# 1_1_1_Interface_board_MCU.net
KiCad netlist of a schematic drawn in Altium Designer
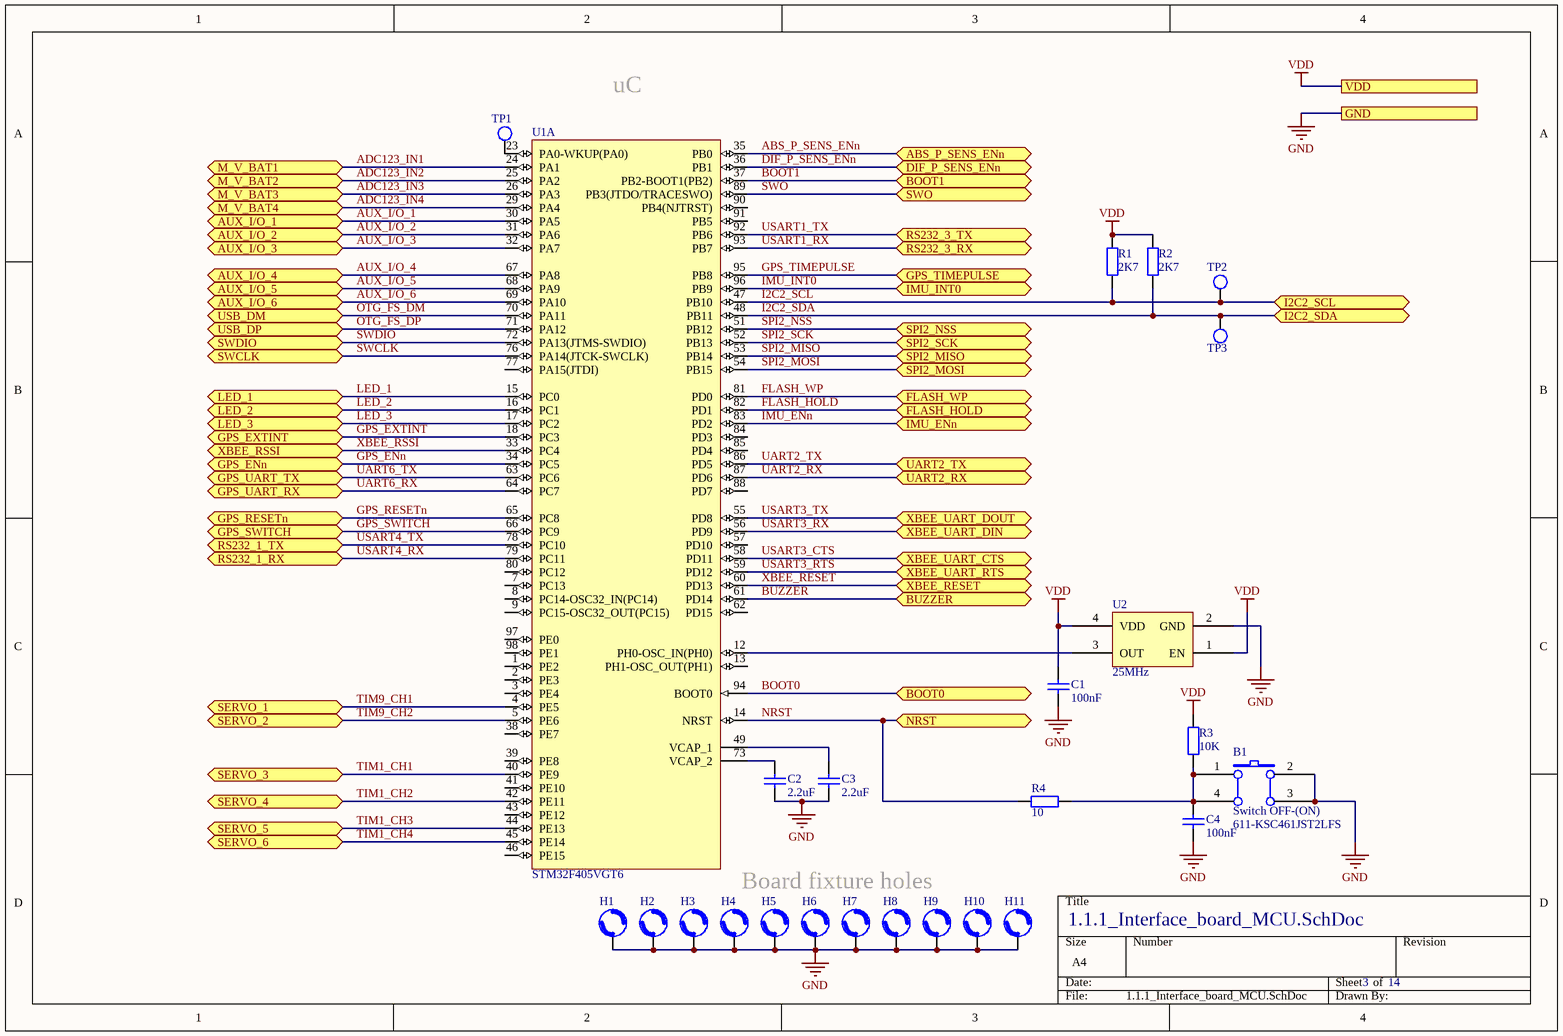
[diagram p0: 1.1.1_Interface_board_MCU.SchDoc]

(export (version "E")
  (design (tool "Eeschema 10.0.6"))
  (components
    (comp (ref "B1")
      (value "Switch OFF-(ON)")
      (footprint "Switch CK")
      (description "OFF-(ON)")
      (fields (field (name "SUPPLIER PART NUMBER 1") "611-KSC461JST2LFS"))
      (libsource (lib "Rocket_library") (part "Switch OFF-(ON)"))
    )
    (comp (ref "C1")
      (value "100nF")
      (footprint "CAP0603R")
      (description "Capacitor")
      (libsource (lib "Rocket_library") (part "C_100nF"))
    )
    (comp (ref "C2")
      (value "2.2uF")
      (footprint "CAP1206W")
      (description "Capacitor")
      (libsource (lib "Rocket_library") (part "C_2.2uF_1206"))
    )
    (comp (ref "C3")
      (value "2.2uF")
      (footprint "CAP1206W")
      (description "Capacitor")
      (libsource (lib "Rocket_library") (part "C_2.2uF_1206"))
    )
    (comp (ref "C4")
      (value "100nF")
      (footprint "CAP0603R")
      (description "Capacitor")
      (libsource (lib "Rocket_library") (part "C_100nF"))
    )
    (comp (ref "H1")
      (value "Hole_3.2mm")
      (footprint "HOLE_3.2mm")
      (libsource (lib "Rocket_library") (part "Hole_3.2mm"))
    )
    (comp (ref "H2")
      (value "Hole_3.2mm")
      (footprint "HOLE_3.2mm")
      (libsource (lib "Rocket_library") (part "Hole_3.2mm"))
    )
    (comp (ref "H3")
      (value "Hole_3.2mm")
      (footprint "HOLE_3.2mm")
      (libsource (lib "Rocket_library") (part "Hole_3.2mm"))
    )
    (comp (ref "H4")
      (value "Hole_3.2mm")
      (footprint "HOLE_3.2mm")
      (libsource (lib "Rocket_library") (part "Hole_3.2mm"))
    )
    (comp (ref "H5")
      (value "Hole_3.2mm")
      (footprint "HOLE_3.2mm")
      (libsource (lib "Rocket_library") (part "Hole_3.2mm"))
    )
    (comp (ref "H6")
      (value "Hole_3.2mm")
      (footprint "HOLE_3.2mm")
      (libsource (lib "Rocket_library") (part "Hole_3.2mm"))
    )
    (comp (ref "H7")
      (value "Hole_3.2mm")
      (footprint "HOLE_3.2mm")
      (libsource (lib "Rocket_library") (part "Hole_3.2mm"))
    )
    (comp (ref "H8")
      (value "Hole_3.2mm")
      (footprint "HOLE_3.2mm")
      (libsource (lib "Rocket_library") (part "Hole_3.2mm"))
    )
    (comp (ref "H9")
      (value "Hole_3.2mm")
      (footprint "HOLE_3.2mm")
      (libsource (lib "Rocket_library") (part "Hole_3.2mm"))
    )
    (comp (ref "H10")
      (value "Hole_3.2mm")
      (footprint "HOLE_3.2mm")
      (libsource (lib "Rocket_library") (part "Hole_3.2mm"))
    )
    (comp (ref "H11")
      (value "Hole_3.2mm")
      (footprint "HOLE_3.2mm")
      (libsource (lib "Rocket_library") (part "Hole_3.2mm"))
    )
    (comp (ref "R1")
      (value "2K7")
      (footprint "0603")
      (description "0.1W 2K7")
      (libsource (lib "Rocket_library") (part "R_0603_01W_2K7"))
    )
    (comp (ref "R2")
      (value "2K7")
      (footprint "0603")
      (description "0.1W 2K7")
      (libsource (lib "Rocket_library") (part "R_0603_01W_2K7"))
    )
    (comp (ref "R3")
      (value "10K")
      (footprint "0603")
      (description "0.1W 10K")
      (libsource (lib "Rocket_library") (part "R_0603_01W_10K"))
    )
    (comp (ref "R4")
      (value "10")
      (footprint "0603")
      (description "0.25W 10Ohm")
      (libsource (lib "Rocket_library") (part "R_0603_025W_10Ohm"))
    )
    (comp (ref "TP1")
      (value "Test point")
      (footprint "TP")
      (libsource (lib "Rocket_library") (part "Test point"))
    )
    (comp (ref "TP2")
      (value "Test point")
      (footprint "TP")
      (libsource (lib "Rocket_library") (part "Test point"))
    )
    (comp (ref "TP3")
      (value "Test point")
      (footprint "TP")
      (libsource (lib "Rocket_library") (part "Test point"))
    )
    (comp (ref "U1")
      (value "STM32F405VGT6")
      (footprint "STM-LQFP100_N")
      (fields (field (name "MANUFACTURER") "STMicroelectronics"))
      (libsource (lib "STMicroelectronics STM32 F4") (part "STM32F405VGT6"))
    )
    (comp (ref "U2")
      (value "25MHz")
      (footprint "SMD_3.2X2.5MM_4P")
      (description "Osc")
      (libsource (lib "Rocket_library") (part "DSC1001CI2-025.0000"))
    )
  )
  (nets
    (net (code "1") (name "/ABS_P_SENS_ENn") (class "Default")
      (node (ref "U1") (pin "35") (pinfunction "PB0_35") (pintype "bidirectional"))
    )
    (net (code "2") (name "/ADC123_IN1") (class "Default")
      (node (ref "U1") (pin "24") (pinfunction "PA1_24") (pintype "bidirectional"))
    )
    (net (code "3") (name "/ADC123_IN2") (class "Default")
      (node (ref "U1") (pin "25") (pinfunction "PA2_25") (pintype "bidirectional"))
    )
    (net (code "4") (name "/ADC123_IN3") (class "Default")
      (node (ref "U1") (pin "26") (pinfunction "PA3_26") (pintype "bidirectional"))
    )
    (net (code "5") (name "/ADC123_IN4") (class "Default")
      (node (ref "U1") (pin "29") (pinfunction "PA4_29") (pintype "bidirectional"))
    )
    (net (code "6") (name "/AUX_I{slash}O_1") (class "Default")
      (node (ref "U1") (pin "30") (pinfunction "PA5_30") (pintype "bidirectional"))
    )
    (net (code "7") (name "/AUX_I{slash}O_2") (class "Default")
      (node (ref "U1") (pin "31") (pinfunction "PA6_31") (pintype "bidirectional"))
    )
    (net (code "8") (name "/AUX_I{slash}O_3") (class "Default")
      (node (ref "U1") (pin "32") (pinfunction "PA7_32") (pintype "bidirectional"))
    )
    (net (code "9") (name "/AUX_I{slash}O_4") (class "Default")
      (node (ref "U1") (pin "67") (pinfunction "PA8_67") (pintype "bidirectional"))
    )
    (net (code "10") (name "/AUX_I{slash}O_5") (class "Default")
      (node (ref "U1") (pin "68") (pinfunction "PA9_68") (pintype "bidirectional"))
    )
    (net (code "11") (name "/AUX_I{slash}O_6") (class "Default")
      (node (ref "U1") (pin "69") (pinfunction "PA10_69") (pintype "bidirectional"))
    )
    (net (code "12") (name "/BOOT0") (class "Default")
      (node (ref "U1") (pin "94") (pinfunction "BOOT0_94") (pintype "input"))
    )
    (net (code "13") (name "/BOOT1") (class "Default")
      (node (ref "U1") (pin "37") (pinfunction "PB2-BOOT1(PB2)_37") (pintype "bidirectional"))
    )
    (net (code "14") (name "/BUZZER") (class "Default")
      (node (ref "U1") (pin "61") (pinfunction "PD14_61") (pintype "bidirectional"))
    )
    (net (code "15") (name "/DIF_P_SENS_ENn") (class "Default")
      (node (ref "U1") (pin "36") (pinfunction "PB1_36") (pintype "bidirectional"))
    )
    (net (code "16") (name "/FLASH_HOLD") (class "Default")
      (node (ref "U1") (pin "82") (pinfunction "PD1_82") (pintype "bidirectional"))
    )
    (net (code "17") (name "/FLASH_WP") (class "Default")
      (node (ref "U1") (pin "81") (pinfunction "PD0_81") (pintype "bidirectional"))
    )
    (net (code "18") (name "/GPS_ENn") (class "Default")
      (node (ref "U1") (pin "34") (pinfunction "PC5_34") (pintype "bidirectional"))
    )
    (net (code "19") (name "/GPS_EXTINT") (class "Default")
      (node (ref "U1") (pin "18") (pinfunction "PC3_18") (pintype "bidirectional"))
    )
    (net (code "20") (name "/GPS_RESETn") (class "Default")
      (node (ref "U1") (pin "65") (pinfunction "PC8_65") (pintype "bidirectional"))
    )
    (net (code "21") (name "/GPS_SWITCH") (class "Default")
      (node (ref "U1") (pin "66") (pinfunction "PC9_66") (pintype "bidirectional"))
    )
    (net (code "22") (name "/GPS_TIMEPULSE") (class "Default")
      (node (ref "U1") (pin "95") (pinfunction "PB8_95") (pintype "bidirectional"))
    )
    (net (code "23") (name "/I2C2_SCL") (class "Default")
      (node (ref "R1") (pin "1") (pinfunction "1_1") (pintype "passive"))
      (node (ref "TP2") (pin "1") (pinfunction "1_1") (pintype "passive"))
      (node (ref "U1") (pin "47") (pinfunction "PB10_47") (pintype "bidirectional"))
    )
    (net (code "24") (name "/I2C2_SDA") (class "Default")
      (node (ref "R2") (pin "1") (pinfunction "1_1") (pintype "passive"))
      (node (ref "TP3") (pin "1") (pinfunction "1_1") (pintype "passive"))
      (node (ref "U1") (pin "48") (pinfunction "PB11_48") (pintype "bidirectional"))
    )
    (net (code "25") (name "/IMU_ENn") (class "Default")
      (node (ref "U1") (pin "83") (pinfunction "PD2_83") (pintype "bidirectional"))
    )
    (net (code "26") (name "/IMU_INT0") (class "Default")
      (node (ref "U1") (pin "96") (pinfunction "PB9_96") (pintype "bidirectional"))
    )
    (net (code "27") (name "/LED_1") (class "Default")
      (node (ref "U1") (pin "15") (pinfunction "PC0_15") (pintype "bidirectional"))
    )
    (net (code "28") (name "/LED_2") (class "Default")
      (node (ref "U1") (pin "16") (pinfunction "PC1_16") (pintype "bidirectional"))
    )
    (net (code "29") (name "/LED_3") (class "Default")
      (node (ref "U1") (pin "17") (pinfunction "PC2_17") (pintype "bidirectional"))
    )
    (net (code "30") (name "/NRST") (class "Default")
      (node (ref "R4") (pin "1") (pinfunction "1_1") (pintype "passive"))
      (node (ref "U1") (pin "14") (pinfunction "NRST_14") (pintype "bidirectional"))
    )
    (net (code "31") (name "/OTG_FS_DM") (class "Default")
      (node (ref "U1") (pin "70") (pinfunction "PA11_70") (pintype "bidirectional"))
    )
    (net (code "32") (name "/OTG_FS_DP") (class "Default")
      (node (ref "U1") (pin "71") (pinfunction "PA12_71") (pintype "bidirectional"))
    )
    (net (code "33") (name "/SPI2_MISO") (class "Default")
      (node (ref "U1") (pin "53") (pinfunction "PB14_53") (pintype "bidirectional"))
    )
    (net (code "34") (name "/SPI2_MOSI") (class "Default")
      (node (ref "U1") (pin "54") (pinfunction "PB15_54") (pintype "bidirectional"))
    )
    (net (code "35") (name "/SPI2_NSS") (class "Default")
      (node (ref "U1") (pin "51") (pinfunction "PB12_51") (pintype "bidirectional"))
    )
    (net (code "36") (name "/SPI2_SCK") (class "Default")
      (node (ref "U1") (pin "52") (pinfunction "PB13_52") (pintype "bidirectional"))
    )
    (net (code "37") (name "/SWCLK") (class "Default")
      (node (ref "U1") (pin "76") (pinfunction "PA14(JTCK-SWCLK)_76") (pintype "bidirectional"))
    )
    (net (code "38") (name "/SWDIO") (class "Default")
      (node (ref "U1") (pin "72") (pinfunction "PA13(JTMS-SWDIO)_72") (pintype "bidirectional"))
    )
    (net (code "39") (name "/SWO") (class "Default")
      (node (ref "U1") (pin "89") (pinfunction "PB3(JTDO/TRACESWO)_89") (pintype "bidirectional"))
    )
    (net (code "40") (name "/TIM1_CH1") (class "Default")
      (node (ref "U1") (pin "40") (pinfunction "PE9_40") (pintype "bidirectional"))
    )
    (net (code "41") (name "/TIM1_CH2") (class "Default")
      (node (ref "U1") (pin "42") (pinfunction "PE11_42") (pintype "bidirectional"))
    )
    (net (code "42") (name "/TIM1_CH3") (class "Default")
      (node (ref "U1") (pin "44") (pinfunction "PE13_44") (pintype "bidirectional"))
    )
    (net (code "43") (name "/TIM1_CH4") (class "Default")
      (node (ref "U1") (pin "45") (pinfunction "PE14_45") (pintype "bidirectional"))
    )
    (net (code "44") (name "/TIM9_CH1") (class "Default")
      (node (ref "U1") (pin "4") (pinfunction "PE5_4") (pintype "bidirectional"))
    )
    (net (code "45") (name "/TIM9_CH2") (class "Default")
      (node (ref "U1") (pin "5") (pinfunction "PE6_5") (pintype "bidirectional"))
    )
    (net (code "46") (name "/UART2_RX") (class "Default")
      (node (ref "U1") (pin "87") (pinfunction "PD6_87") (pintype "bidirectional"))
    )
    (net (code "47") (name "/UART2_TX") (class "Default")
      (node (ref "U1") (pin "86") (pinfunction "PD5_86") (pintype "bidirectional"))
    )
    (net (code "48") (name "/UART6_RX") (class "Default")
      (node (ref "U1") (pin "64") (pinfunction "PC7_64") (pintype "bidirectional"))
    )
    (net (code "49") (name "/UART6_TX") (class "Default")
      (node (ref "U1") (pin "63") (pinfunction "PC6_63") (pintype "bidirectional"))
    )
    (net (code "50") (name "/USART1_RX") (class "Default")
      (node (ref "U1") (pin "93") (pinfunction "PB7_93") (pintype "bidirectional"))
    )
    (net (code "51") (name "/USART1_TX") (class "Default")
      (node (ref "U1") (pin "92") (pinfunction "PB6_92") (pintype "bidirectional"))
    )
    (net (code "52") (name "/USART3_CTS") (class "Default")
      (node (ref "U1") (pin "58") (pinfunction "PD11_58") (pintype "bidirectional"))
    )
    (net (code "53") (name "/USART3_RTS") (class "Default")
      (node (ref "U1") (pin "59") (pinfunction "PD12_59") (pintype "bidirectional"))
    )
    (net (code "54") (name "/USART3_RX") (class "Default")
      (node (ref "U1") (pin "56") (pinfunction "PD9_56") (pintype "bidirectional"))
    )
    (net (code "55") (name "/USART3_TX") (class "Default")
      (node (ref "U1") (pin "55") (pinfunction "PD8_55") (pintype "bidirectional"))
    )
    (net (code "56") (name "/USART4_RX") (class "Default")
      (node (ref "U1") (pin "79") (pinfunction "PC11_79") (pintype "bidirectional"))
    )
    (net (code "57") (name "/USART4_TX") (class "Default")
      (node (ref "U1") (pin "78") (pinfunction "PC10_78") (pintype "bidirectional"))
    )
    (net (code "58") (name "/XBEE_RESET") (class "Default")
      (node (ref "U1") (pin "60") (pinfunction "PD13_60") (pintype "bidirectional"))
    )
    (net (code "59") (name "/XBEE_RSSI") (class "Default")
      (node (ref "U1") (pin "33") (pinfunction "PC4_33") (pintype "bidirectional"))
    )
    (net (code "60") (name "GND") (class "Default")
      (node (ref "B1") (pin "2") (pinfunction "B0_2") (pintype "passive"))
      (node (ref "B1") (pin "3") (pinfunction "B1_3") (pintype "passive"))
      (node (ref "C1") (pin "1") (pinfunction "1_1") (pintype "passive"))
      (node (ref "C2") (pin "1") (pinfunction "1_1") (pintype "passive"))
      (node (ref "C3") (pin "1") (pinfunction "1_1") (pintype "passive"))
      (node (ref "C4") (pin "2") (pinfunction "2_2") (pintype "passive"))
      (node (ref "H1") (pin "0") (pinfunction "0_0") (pintype "passive"))
      (node (ref "H10") (pin "0") (pinfunction "0_0") (pintype "passive"))
      (node (ref "H11") (pin "0") (pinfunction "0_0") (pintype "passive"))
      (node (ref "H2") (pin "0") (pinfunction "0_0") (pintype "passive"))
      (node (ref "H3") (pin "0") (pinfunction "0_0") (pintype "passive"))
      (node (ref "H4") (pin "0") (pinfunction "0_0") (pintype "passive"))
      (node (ref "H5") (pin "0") (pinfunction "0_0") (pintype "passive"))
      (node (ref "H6") (pin "0") (pinfunction "0_0") (pintype "passive"))
      (node (ref "H7") (pin "0") (pinfunction "0_0") (pintype "passive"))
      (node (ref "H8") (pin "0") (pinfunction "0_0") (pintype "passive"))
      (node (ref "H9") (pin "0") (pinfunction "0_0") (pintype "passive"))
      (node (ref "U2") (pin "2") (pinfunction "GND_2") (pintype "passive"))
    )
    (net (code "61") (name "Net-(B1-A0)") (class "Default")
      (node (ref "B1") (pin "1") (pinfunction "A0_1") (pintype "passive"))
      (node (ref "B1") (pin "4") (pinfunction "A1_4") (pintype "passive"))
      (node (ref "C4") (pin "1") (pinfunction "1_1") (pintype "passive"))
      (node (ref "R3") (pin "1") (pinfunction "1_1") (pintype "passive"))
      (node (ref "R4") (pin "2") (pinfunction "2_2") (pintype "passive"))
    )
    (net (code "62") (name "Net-(U1A-PA0-WKUP(PA0))") (class "Default")
      (node (ref "TP1") (pin "1") (pinfunction "1_1") (pintype "passive"))
      (node (ref "U1") (pin "23") (pinfunction "PA0-WKUP(PA0)_23") (pintype "bidirectional"))
    )
    (net (code "63") (name "Net-(U1A-PH0-OSC_IN(PH0))") (class "Default")
      (node (ref "U1") (pin "12") (pinfunction "PH0-OSC_IN(PH0)_12") (pintype "bidirectional"))
      (node (ref "U2") (pin "3") (pinfunction "OUT_3") (pintype "passive"))
    )
    (net (code "64") (name "Net-(U1A-VCAP_1)") (class "Default")
      (node (ref "C3") (pin "2") (pinfunction "2_2") (pintype "passive"))
      (node (ref "U1") (pin "49") (pinfunction "VCAP_1_49") (pintype "power_in"))
    )
    (net (code "65") (name "Net-(U1A-VCAP_2)") (class "Default")
      (node (ref "C2") (pin "2") (pinfunction "2_2") (pintype "passive"))
      (node (ref "U1") (pin "73") (pinfunction "VCAP_2_73") (pintype "power_in"))
    )
    (net (code "66") (name "VDD") (class "Default")
      (node (ref "C1") (pin "2") (pinfunction "2_2") (pintype "passive"))
      (node (ref "R1") (pin "2") (pinfunction "2_2") (pintype "passive"))
      (node (ref "R2") (pin "2") (pinfunction "2_2") (pintype "passive"))
      (node (ref "R3") (pin "2") (pinfunction "2_2") (pintype "passive"))
      (node (ref "U2") (pin "1") (pinfunction "EN_1") (pintype "passive"))
      (node (ref "U2") (pin "4") (pinfunction "VDD_4") (pintype "passive"))
    )
    (net (code "67") (name "unconnected-(U1A-PA15(JTDI)-Pad77)") (class "Default")
      (node (ref "U1") (pin "77") (pinfunction "PA15(JTDI)_77") (pintype "bidirectional"))
    )
    (net (code "68") (name "unconnected-(U1A-PB4(NJTRST)-Pad90)") (class "Default")
      (node (ref "U1") (pin "90") (pinfunction "PB4(NJTRST)_90") (pintype "bidirectional"))
    )
    (net (code "69") (name "unconnected-(U1A-PB5-Pad91)") (class "Default")
      (node (ref "U1") (pin "91") (pinfunction "PB5_91") (pintype "bidirectional"))
    )
    (net (code "70") (name "unconnected-(U1A-PC12-Pad80)") (class "Default")
      (node (ref "U1") (pin "80") (pinfunction "PC12_80") (pintype "bidirectional"))
    )
    (net (code "71") (name "unconnected-(U1A-PC13-Pad7)") (class "Default")
      (node (ref "U1") (pin "7") (pinfunction "PC13_7") (pintype "bidirectional"))
    )
    (net (code "72") (name "unconnected-(U1A-PC14-OSC32_IN(PC14)-Pad8)") (class "Default")
      (node (ref "U1") (pin "8") (pinfunction "PC14-OSC32_IN(PC14)_8") (pintype "bidirectional"))
    )
    (net (code "73") (name "unconnected-(U1A-PC15-OSC32_OUT(PC15)-Pad9)") (class "Default")
      (node (ref "U1") (pin "9") (pinfunction "PC15-OSC32_OUT(PC15)_9") (pintype "bidirectional"))
    )
    (net (code "74") (name "unconnected-(U1A-PD3-Pad84)") (class "Default")
      (node (ref "U1") (pin "84") (pinfunction "PD3_84") (pintype "bidirectional"))
    )
    (net (code "75") (name "unconnected-(U1A-PD4-Pad85)") (class "Default")
      (node (ref "U1") (pin "85") (pinfunction "PD4_85") (pintype "bidirectional"))
    )
    (net (code "76") (name "unconnected-(U1A-PD7-Pad88)") (class "Default")
      (node (ref "U1") (pin "88") (pinfunction "PD7_88") (pintype "bidirectional"))
    )
    (net (code "77") (name "unconnected-(U1A-PD10-Pad57)") (class "Default")
      (node (ref "U1") (pin "57") (pinfunction "PD10_57") (pintype "bidirectional"))
    )
    (net (code "78") (name "unconnected-(U1A-PD15-Pad62)") (class "Default")
      (node (ref "U1") (pin "62") (pinfunction "PD15_62") (pintype "bidirectional"))
    )
    (net (code "79") (name "unconnected-(U1A-PE0-Pad97)") (class "Default")
      (node (ref "U1") (pin "97") (pinfunction "PE0_97") (pintype "bidirectional"))
    )
    (net (code "80") (name "unconnected-(U1A-PE1-Pad98)") (class "Default")
      (node (ref "U1") (pin "98") (pinfunction "PE1_98") (pintype "bidirectional"))
    )
    (net (code "81") (name "unconnected-(U1A-PE2-Pad1)") (class "Default")
      (node (ref "U1") (pin "1") (pinfunction "PE2_1") (pintype "bidirectional"))
    )
    (net (code "82") (name "unconnected-(U1A-PE3-Pad2)") (class "Default")
      (node (ref "U1") (pin "2") (pinfunction "PE3_2") (pintype "bidirectional"))
    )
    (net (code "83") (name "unconnected-(U1A-PE4-Pad3)") (class "Default")
      (node (ref "U1") (pin "3") (pinfunction "PE4_3") (pintype "bidirectional"))
    )
    (net (code "84") (name "unconnected-(U1A-PE7-Pad38)") (class "Default")
      (node (ref "U1") (pin "38") (pinfunction "PE7_38") (pintype "bidirectional"))
    )
    (net (code "85") (name "unconnected-(U1A-PE8-Pad39)") (class "Default")
      (node (ref "U1") (pin "39") (pinfunction "PE8_39") (pintype "bidirectional"))
    )
    (net (code "86") (name "unconnected-(U1A-PE10-Pad41)") (class "Default")
      (node (ref "U1") (pin "41") (pinfunction "PE10_41") (pintype "bidirectional"))
    )
    (net (code "87") (name "unconnected-(U1A-PE12-Pad43)") (class "Default")
      (node (ref "U1") (pin "43") (pinfunction "PE12_43") (pintype "bidirectional"))
    )
    (net (code "88") (name "unconnected-(U1A-PE15-Pad46)") (class "Default")
      (node (ref "U1") (pin "46") (pinfunction "PE15_46") (pintype "bidirectional"))
    )
    (net (code "89") (name "unconnected-(U1A-PH1-OSC_OUT(PH1)-Pad13)") (class "Default")
      (node (ref "U1") (pin "13") (pinfunction "PH1-OSC_OUT(PH1)_13") (pintype "bidirectional"))
    )
  )
)
